# Sheet2.net
KiCad netlist of a schematic drawn in Altium Designer
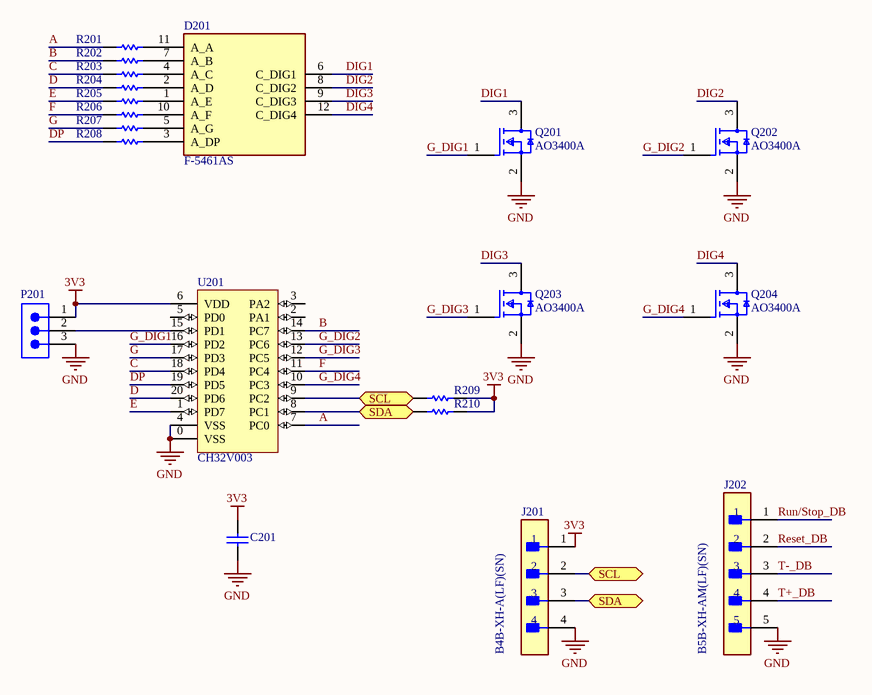
[diagram p0: Sheet2.SchDoc]

(export (version "E")
  (design (tool "Eeschema 10.0.6"))
  (components
    (comp (ref "C201")
      (value "Capacitor")
      (footprint "CAPC1608X09N")
      (libsource (lib "Schlib1") (part "C0603"))
    )
    (comp (ref "D201")
      (value "F-5461AS")
      (footprint "5461AS")
      (description "Quad LED 7-Segment Display")
      (libsource (lib "Schlib1") (part "5461AS"))
    )
    (comp (ref "J201")
      (value "B4B-XH-A(LF)(SN)")
      (footprint "FP-B4B-XH-A_LF_SN-MFG")
      (description "CONN HEADER VERT 4POS 2.5MM")
      (libsource (lib "Altium Content Vault") (part "299a8cea1bdcbc3624fe62c390fa72c"))
    )
    (comp (ref "J202")
      (value "B5B-XH-AM(LF)(SN)")
      (footprint "FP-B5B-XH-AM_LF_SN-MFG")
      (description "CONN HEADER VERT 5POS 2.5MM")
      (libsource (lib "Altium Content Vault") (part "bf93c07fd2649a848d0ec8585582aab"))
    )
    (comp (ref "P201")
      (value "61300311121")
      (footprint "61300311121")
      (libsource (lib "Altium Content Vault") (part "Header_Male_1R_03P"))
    )
    (comp (ref "Q201")
      (value "AO3400A")
      (footprint "FP-SOT23-MFG")
      (description "MOSFET N-CH 30V 5.7A SOT23")
      (libsource (lib "Altium Content Vault") (part "0a9ea7c96deaaede766a5b531c28de0"))
    )
    (comp (ref "Q202")
      (value "AO3400A")
      (footprint "FP-SOT23-MFG")
      (description "MOSFET N-CH 30V 5.7A SOT23")
      (libsource (lib "Altium Content Vault") (part "0a9ea7c96deaaede766a5b531c28de0"))
    )
    (comp (ref "Q203")
      (value "AO3400A")
      (footprint "FP-SOT23-MFG")
      (description "MOSFET N-CH 30V 5.7A SOT23")
      (libsource (lib "Altium Content Vault") (part "0a9ea7c96deaaede766a5b531c28de0"))
    )
    (comp (ref "Q204")
      (value "AO3400A")
      (footprint "FP-SOT23-MFG")
      (description "MOSFET N-CH 30V 5.7A SOT23")
      (libsource (lib "Altium Content Vault") (part "0a9ea7c96deaaede766a5b531c28de0"))
    )
    (comp (ref "R201")
      (value "Resistor")
      (footprint "RESC1608X06N")
      (libsource (lib "Schlib1") (part "R0603"))
    )
    (comp (ref "R202")
      (value "Resistor")
      (footprint "RESC1608X06N")
      (libsource (lib "Schlib1") (part "R0603"))
    )
    (comp (ref "R203")
      (value "Resistor")
      (footprint "RESC1608X06N")
      (libsource (lib "Schlib1") (part "R0603"))
    )
    (comp (ref "R204")
      (value "Resistor")
      (footprint "RESC1608X06N")
      (libsource (lib "Schlib1") (part "R0603"))
    )
    (comp (ref "R205")
      (value "Resistor")
      (footprint "RESC1608X06N")
      (libsource (lib "Schlib1") (part "R0603"))
    )
    (comp (ref "R206")
      (value "Resistor")
      (footprint "RESC1608X06N")
      (libsource (lib "Schlib1") (part "R0603"))
    )
    (comp (ref "R207")
      (value "Resistor")
      (footprint "RESC1608X06N")
      (libsource (lib "Schlib1") (part "R0603"))
    )
    (comp (ref "R208")
      (value "Resistor")
      (footprint "RESC1608X06N")
      (libsource (lib "Schlib1") (part "R0603"))
    )
    (comp (ref "R209")
      (value "Resistor")
      (footprint "RESC1608X06N")
      (libsource (lib "Schlib1") (part "R0603"))
    )
    (comp (ref "R210")
      (value "Resistor")
      (footprint "RESC1608X06N")
      (libsource (lib "Schlib1") (part "R0603"))
    )
    (comp (ref "U201")
      (value "CH32V003")
      (footprint "QFN40P300X300X75_HS-21N")
      (libsource (lib "Schlib1") (part "CH32V003F4U6"))
    )
  )
  (nets
    (net (code "1") (name "/A") (class "Default")
      (node (ref "R201") (pin "1") (pintype "passive"))
      (node (ref "U201") (pin "7") (pinfunction "PC0_7") (pintype "bidirectional"))
    )
    (net (code "2") (name "/B") (class "Default")
      (node (ref "R202") (pin "1") (pintype "passive"))
      (node (ref "U201") (pin "14") (pinfunction "PC7_14") (pintype "bidirectional"))
    )
    (net (code "3") (name "/C") (class "Default")
      (node (ref "R203") (pin "1") (pintype "passive"))
      (node (ref "U201") (pin "18") (pinfunction "PD4_18") (pintype "bidirectional"))
    )
    (net (code "4") (name "/D") (class "Default")
      (node (ref "R204") (pin "1") (pintype "passive"))
      (node (ref "U201") (pin "20") (pinfunction "PD6_20") (pintype "bidirectional"))
    )
    (net (code "5") (name "/DIG1") (class "Default")
      (node (ref "D201") (pin "6") (pinfunction "C_DIG1_6") (pintype "passive"))
      (node (ref "Q201") (pin "3") (pinfunction "D_3") (pintype "passive"))
    )
    (net (code "6") (name "/DIG2") (class "Default")
      (node (ref "D201") (pin "8") (pinfunction "C_DIG2_8") (pintype "passive"))
      (node (ref "Q202") (pin "3") (pinfunction "D_3") (pintype "passive"))
    )
    (net (code "7") (name "/DIG3") (class "Default")
      (node (ref "D201") (pin "9") (pinfunction "C_DIG3_9") (pintype "passive"))
      (node (ref "Q203") (pin "3") (pinfunction "D_3") (pintype "passive"))
    )
    (net (code "8") (name "/DIG4") (class "Default")
      (node (ref "D201") (pin "12") (pinfunction "C_DIG4_12") (pintype "passive"))
      (node (ref "Q204") (pin "3") (pinfunction "D_3") (pintype "passive"))
    )
    (net (code "9") (name "/DP") (class "Default")
      (node (ref "R208") (pin "1") (pintype "passive"))
      (node (ref "U201") (pin "19") (pinfunction "PD5_19") (pintype "bidirectional"))
    )
    (net (code "10") (name "/E") (class "Default")
      (node (ref "R205") (pin "1") (pintype "passive"))
      (node (ref "U201") (pin "1") (pinfunction "PD7_1") (pintype "bidirectional"))
    )
    (net (code "11") (name "/F") (class "Default")
      (node (ref "R206") (pin "1") (pintype "passive"))
      (node (ref "U201") (pin "11") (pinfunction "PC4_11") (pintype "bidirectional"))
    )
    (net (code "12") (name "/G") (class "Default")
      (node (ref "R207") (pin "1") (pintype "passive"))
      (node (ref "U201") (pin "17") (pinfunction "PD3_17") (pintype "bidirectional"))
    )
    (net (code "13") (name "/G_DIG1") (class "Default")
      (node (ref "Q201") (pin "1") (pinfunction "G_1") (pintype "passive"))
      (node (ref "U201") (pin "16") (pinfunction "PD2_16") (pintype "bidirectional"))
    )
    (net (code "14") (name "/G_DIG2") (class "Default")
      (node (ref "Q202") (pin "1") (pinfunction "G_1") (pintype "passive"))
      (node (ref "U201") (pin "13") (pinfunction "PC6_13") (pintype "bidirectional"))
    )
    (net (code "15") (name "/G_DIG3") (class "Default")
      (node (ref "Q203") (pin "1") (pinfunction "G_1") (pintype "passive"))
      (node (ref "U201") (pin "12") (pinfunction "PC5_12") (pintype "bidirectional"))
    )
    (net (code "16") (name "/G_DIG4") (class "Default")
      (node (ref "Q204") (pin "1") (pinfunction "G_1") (pintype "passive"))
      (node (ref "U201") (pin "10") (pinfunction "PC3_10") (pintype "bidirectional"))
    )
    (net (code "17") (name "/Reset_DB") (class "Default")
      (node (ref "J202") (pin "2") (pinfunction "2_2") (pintype "passive"))
    )
    (net (code "18") (name "/Run{slash}Stop_DB") (class "Default")
      (node (ref "J202") (pin "1") (pinfunction "1_1") (pintype "passive"))
    )
    (net (code "19") (name "/SCL") (class "Default")
      (node (ref "J201") (pin "2") (pinfunction "2_2") (pintype "passive"))
      (node (ref "R209") (pin "1") (pintype "passive"))
      (node (ref "U201") (pin "9") (pinfunction "PC2_9") (pintype "bidirectional"))
    )
    (net (code "20") (name "/SDA") (class "Default")
      (node (ref "J201") (pin "3") (pinfunction "3_3") (pintype "passive"))
      (node (ref "R210") (pin "1") (pintype "passive"))
      (node (ref "U201") (pin "8") (pinfunction "PC1_8") (pintype "bidirectional"))
    )
    (net (code "21") (name "/T+_DB") (class "Default")
      (node (ref "J202") (pin "4") (pinfunction "4_4") (pintype "passive"))
    )
    (net (code "22") (name "/T-_DB") (class "Default")
      (node (ref "J202") (pin "3") (pinfunction "3_3") (pintype "passive"))
    )
    (net (code "23") (name "3V3") (class "Default")
      (node (ref "C201") (pin "2") (pintype "passive"))
      (node (ref "J201") (pin "1") (pinfunction "1_1") (pintype "passive"))
      (node (ref "P201") (pin "1") (pinfunction "1_1") (pintype "passive"))
      (node (ref "R209") (pin "2") (pintype "passive"))
      (node (ref "R210") (pin "2") (pintype "passive"))
      (node (ref "U201") (pin "6") (pinfunction "VDD_6") (pintype "power_in"))
    )
    (net (code "24") (name "GND") (class "Default")
      (node (ref "C201") (pin "1") (pintype "passive"))
      (node (ref "J201") (pin "4") (pinfunction "4_4") (pintype "passive"))
      (node (ref "J202") (pin "5") (pinfunction "5_5") (pintype "passive"))
      (node (ref "P201") (pin "3") (pinfunction "3_3") (pintype "passive"))
      (node (ref "Q201") (pin "2") (pinfunction "S_2") (pintype "passive"))
      (node (ref "Q202") (pin "2") (pinfunction "S_2") (pintype "passive"))
      (node (ref "Q203") (pin "2") (pinfunction "S_2") (pintype "passive"))
      (node (ref "Q204") (pin "2") (pinfunction "S_2") (pintype "passive"))
      (node (ref "U201") (pin "0") (pinfunction "VSS_0") (pintype "power_in"))
      (node (ref "U201") (pin "4") (pinfunction "VSS_4") (pintype "power_in"))
    )
    (net (code "25") (name "Net-(D201-A_A)") (class "Default")
      (node (ref "D201") (pin "11") (pinfunction "A_A_11") (pintype "passive"))
      (node (ref "R201") (pin "2") (pintype "passive"))
    )
    (net (code "26") (name "Net-(D201-A_B)") (class "Default")
      (node (ref "D201") (pin "7") (pinfunction "A_B_7") (pintype "passive"))
      (node (ref "R202") (pin "2") (pintype "passive"))
    )
    (net (code "27") (name "Net-(D201-A_C)") (class "Default")
      (node (ref "D201") (pin "4") (pinfunction "A_C_4") (pintype "passive"))
      (node (ref "R203") (pin "2") (pintype "passive"))
    )
    (net (code "28") (name "Net-(D201-A_D)") (class "Default")
      (node (ref "D201") (pin "2") (pinfunction "A_D_2") (pintype "passive"))
      (node (ref "R204") (pin "2") (pintype "passive"))
    )
    (net (code "29") (name "Net-(D201-A_DP)") (class "Default")
      (node (ref "D201") (pin "3") (pinfunction "A_DP_3") (pintype "passive"))
      (node (ref "R208") (pin "2") (pintype "passive"))
    )
    (net (code "30") (name "Net-(D201-A_E)") (class "Default")
      (node (ref "D201") (pin "1") (pinfunction "A_E_1") (pintype "passive"))
      (node (ref "R205") (pin "2") (pintype "passive"))
    )
    (net (code "31") (name "Net-(D201-A_F)") (class "Default")
      (node (ref "D201") (pin "10") (pinfunction "A_F_10") (pintype "passive"))
      (node (ref "R206") (pin "2") (pintype "passive"))
    )
    (net (code "32") (name "Net-(D201-A_G)") (class "Default")
      (node (ref "D201") (pin "5") (pinfunction "A_G_5") (pintype "passive"))
      (node (ref "R207") (pin "2") (pintype "passive"))
    )
    (net (code "33") (name "Net-(U201-PD1)") (class "Default")
      (node (ref "P201") (pin "2") (pinfunction "2_2") (pintype "passive"))
      (node (ref "U201") (pin "15") (pinfunction "PD1_15") (pintype "bidirectional"))
    )
    (net (code "34") (name "unconnected-(U201-PA1-Pad2)") (class "Default")
      (node (ref "U201") (pin "2") (pinfunction "PA1_2") (pintype "bidirectional"))
    )
    (net (code "35") (name "unconnected-(U201-PA2-Pad3)") (class "Default")
      (node (ref "U201") (pin "3") (pinfunction "PA2_3") (pintype "bidirectional"))
    )
    (net (code "36") (name "unconnected-(U201-PD0-Pad5)") (class "Default")
      (node (ref "U201") (pin "5") (pinfunction "PD0_5") (pintype "bidirectional"))
    )
  )
)
